# 06_FPGA_POWER.net
KiCad netlist of a schematic drawn in Altium Designer
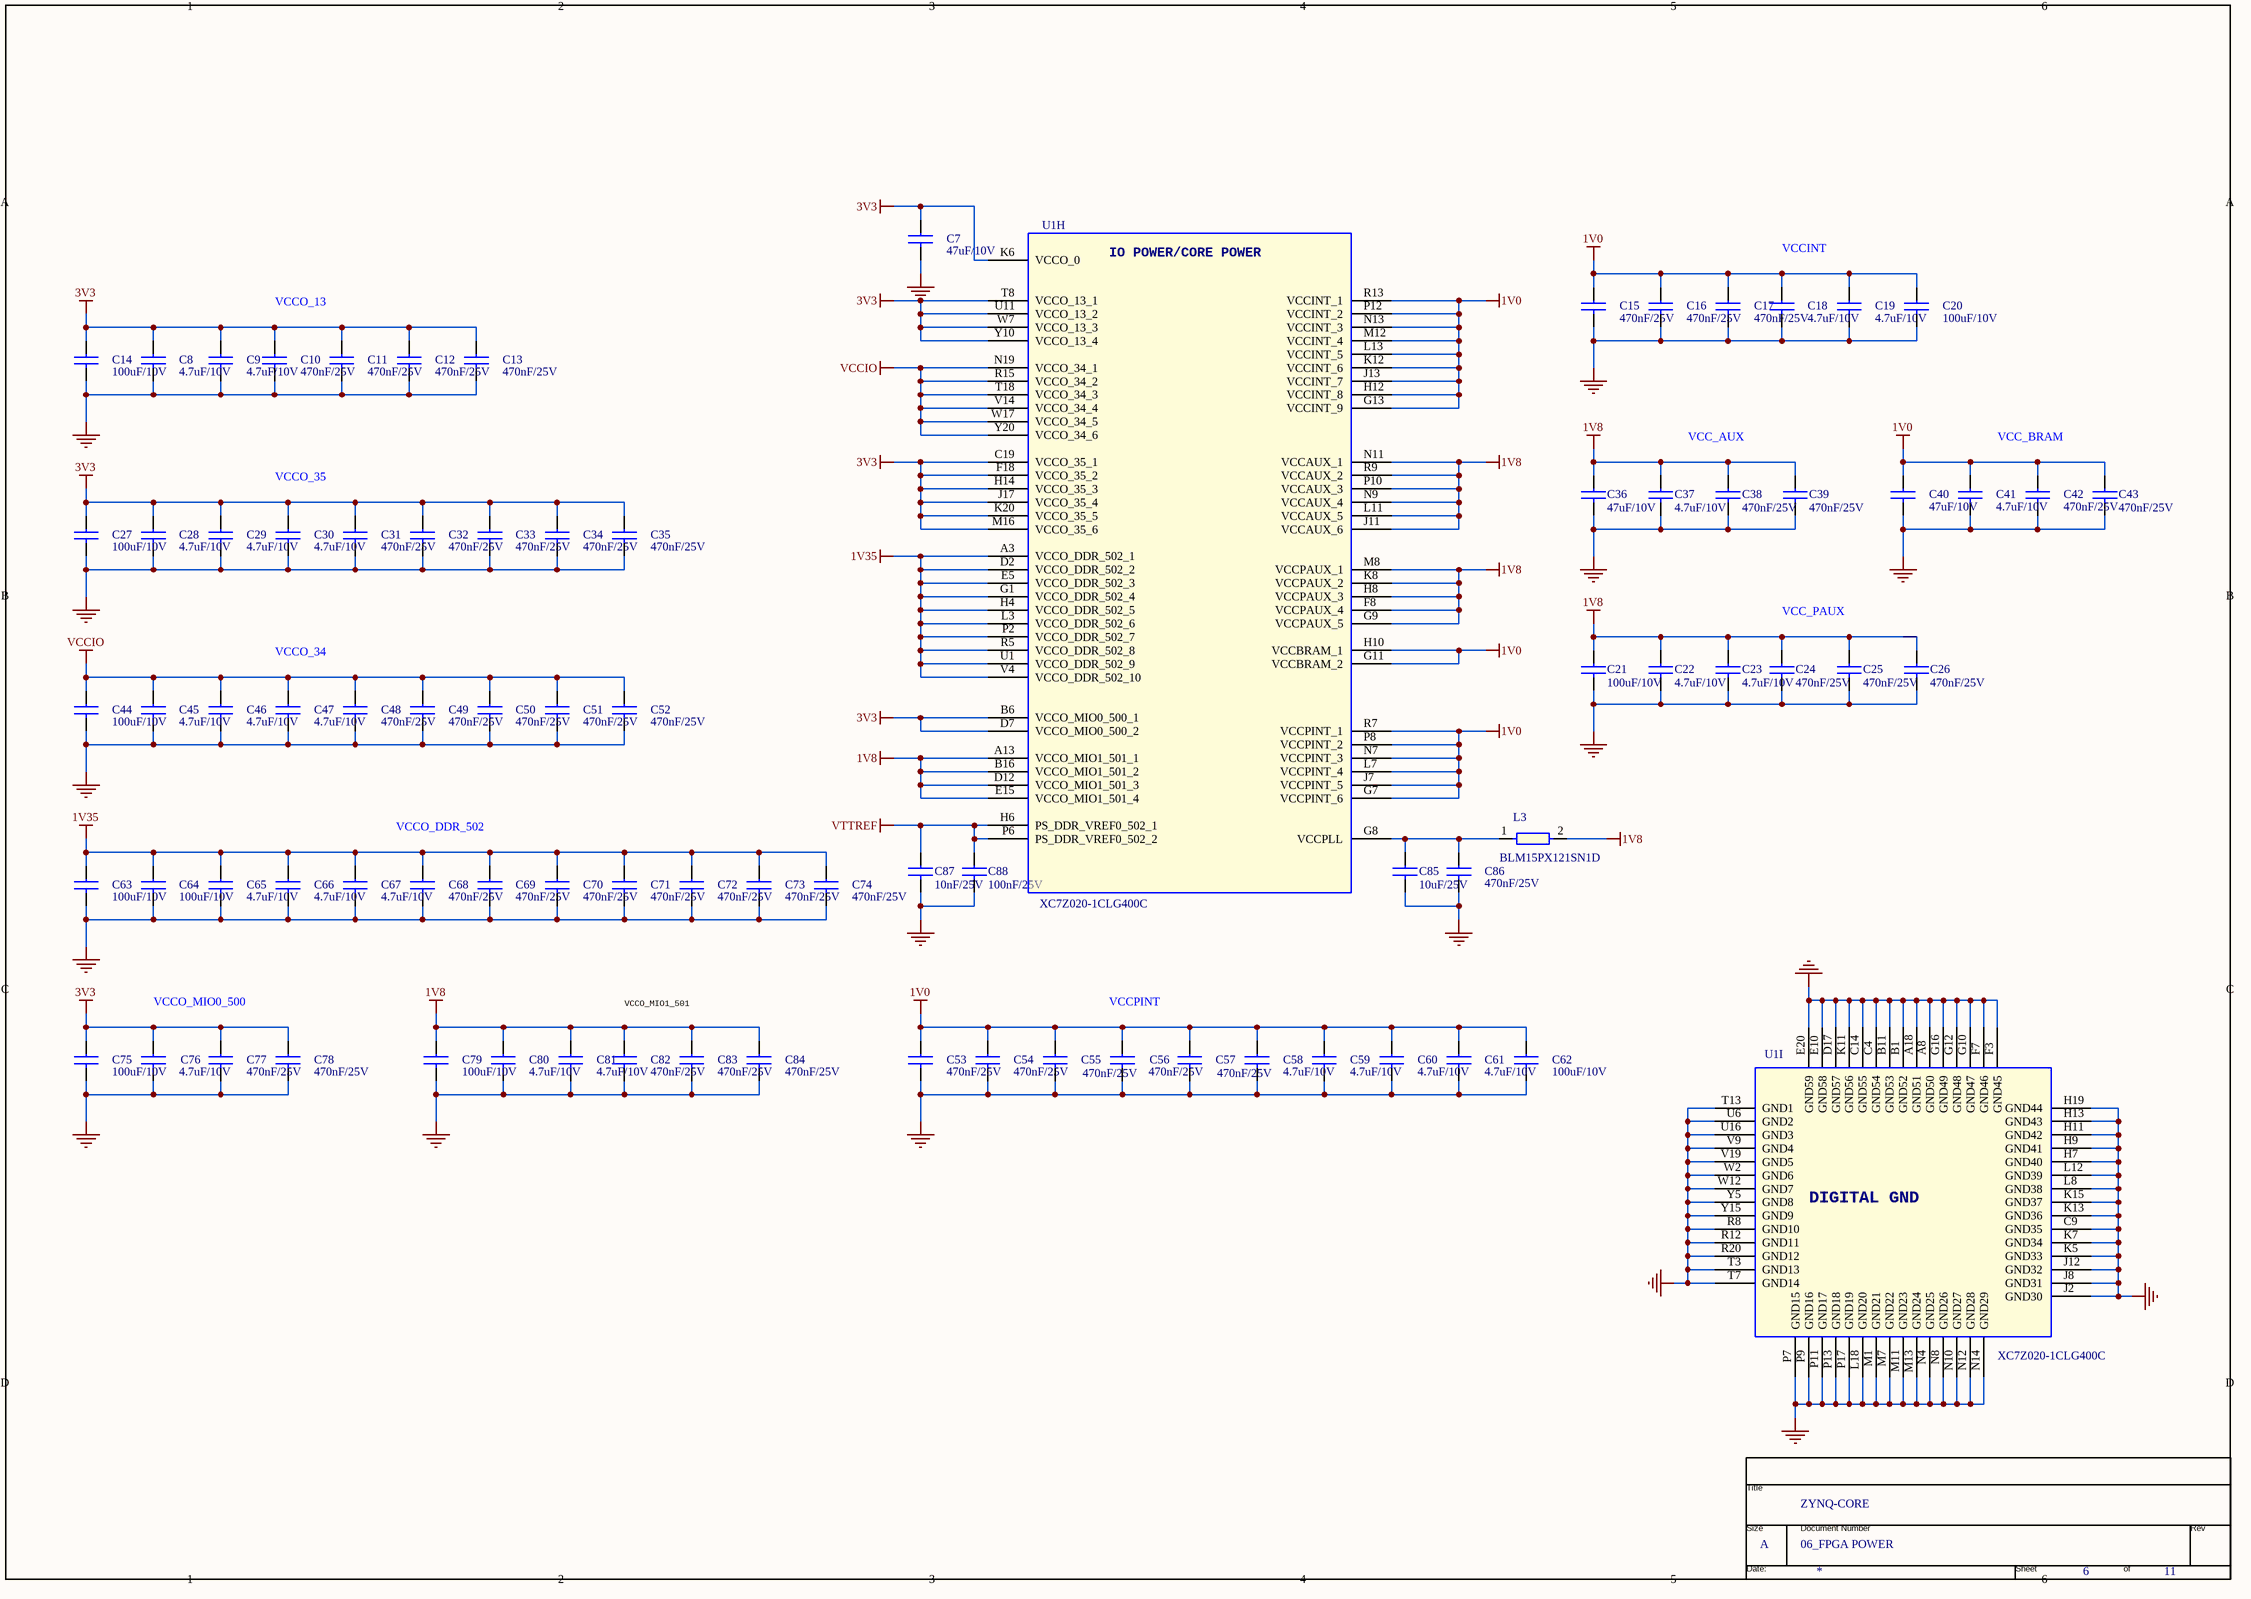
[diagram p0: 06_FPGA POWER.SchDoc]

(export (version "E")
  (design (tool "Eeschema 10.0.6"))
  (components
    (comp (ref "C7") (value "47uF/10V") (footprint "C0805") (libsource (lib "*") (part "CAP NP_Dup1")))
    (comp (ref "C8") (value "4.7uF/10V") (footprint "C0402") (libsource (lib "*") (part "CAP NP_Dup1")))
    (comp (ref "C9") (value "4.7uF/10V") (footprint "C0402") (libsource (lib "*") (part "CAP NP_Dup1")))
    (comp (ref "C10") (value "470nF/25V") (footprint "C0402") (libsource (lib "*") (part "CAP NP_Dup1")))
    (comp (ref "C11") (value "470nF/25V") (footprint "C0402") (libsource (lib "*") (part "CAP NP_Dup1")))
    (comp (ref "C12") (value "470nF/25V") (footprint "C0402") (libsource (lib "*") (part "CAP NP_Dup1")))
    (comp (ref "C13") (value "470nF/25V") (footprint "C0402") (libsource (lib "*") (part "CAP NP_Dup1")))
    (comp (ref "C14") (value "100uF/10V") (footprint "1206C-N") (libsource (lib "*") (part "CAP NP_Dup1")))
    (comp (ref "C15") (value "470nF/25V") (footprint "C0402") (libsource (lib "*") (part "CAP NP_Dup1")))
    (comp (ref "C16") (value "470nF/25V") (footprint "C0402") (libsource (lib "*") (part "CAP NP_Dup1")))
    (comp (ref "C17") (value "470nF/25V") (footprint "C0402") (libsource (lib "*") (part "CAP NP_Dup1")))
    (comp (ref "C18") (value "4.7uF/10V") (footprint "C0402") (libsource (lib "*") (part "CAP NP_Dup1")))
    (comp (ref "C19") (value "4.7uF/10V") (footprint "C0402") (libsource (lib "*") (part "CAP NP_Dup1")))
    (comp (ref "C20") (value "100uF/10V") (footprint "1206C-N") (libsource (lib "*") (part "CAP NP_Dup1")))
    (comp (ref "C21") (value "100uF/10V") (footprint "1206C-N") (libsource (lib "*") (part "CAP NP_Dup1")))
    (comp (ref "C22") (value "4.7uF/10V") (footprint "C0402") (libsource (lib "*") (part "CAP NP_Dup1")))
    (comp (ref "C23") (value "4.7uF/10V") (footprint "C0402") (libsource (lib "*") (part "CAP NP_Dup1")))
    (comp (ref "C24") (value "470nF/25V") (footprint "C0402") (libsource (lib "*") (part "CAP NP_Dup1")))
    (comp (ref "C25") (value "470nF/25V") (footprint "C0402") (libsource (lib "*") (part "CAP NP_Dup1")))
    (comp (ref "C26") (value "470nF/25V") (footprint "C0402") (libsource (lib "*") (part "CAP NP_Dup1")))
    (comp (ref "C27") (value "100uF/10V") (footprint "1206C-N") (libsource (lib "*") (part "CAP NP_Dup1")))
    (comp (ref "C28") (value "4.7uF/10V") (footprint "C0402") (libsource (lib "*") (part "CAP NP_Dup1")))
    (comp (ref "C29") (value "4.7uF/10V") (footprint "C0402") (libsource (lib "*") (part "CAP NP_Dup1")))
    (comp (ref "C30") (value "4.7uF/10V") (footprint "C0402") (libsource (lib "*") (part "CAP NP_Dup1")))
    (comp (ref "C31") (value "470nF/25V") (footprint "C0402") (libsource (lib "*") (part "CAP NP_Dup1")))
    (comp (ref "C32") (value "470nF/25V") (footprint "C0402") (libsource (lib "*") (part "CAP NP_Dup1")))
    (comp (ref "C33") (value "470nF/25V") (footprint "C0402") (libsource (lib "*") (part "CAP NP_Dup1")))
    (comp (ref "C34") (value "470nF/25V") (footprint "C0402") (libsource (lib "*") (part "CAP NP_Dup1")))
    (comp (ref "C35") (value "470nF/25V") (footprint "C0402") (libsource (lib "*") (part "CAP NP_Dup1")))
    (comp (ref "C36") (value "47uF/10V") (footprint "C0805") (libsource (lib "*") (part "CAP NP_Dup1")))
    (comp (ref "C37") (value "4.7uF/10V") (footprint "C0402") (libsource (lib "*") (part "CAP NP_Dup1")))
    (comp (ref "C38") (value "470nF/25V") (footprint "C0402") (libsource (lib "*") (part "CAP NP_Dup1")))
    (comp (ref "C39") (value "470nF/25V") (footprint "C0402") (libsource (lib "*") (part "CAP NP_Dup1")))
    (comp (ref "C40") (value "47uF/10V") (footprint "C0805") (libsource (lib "*") (part "CAP NP_Dup1")))
    (comp (ref "C41") (value "4.7uF/10V") (footprint "C0402") (libsource (lib "*") (part "CAP NP_Dup1")))
    (comp (ref "C42") (value "470nF/25V") (footprint "C0402") (libsource (lib "*") (part "CAP NP_Dup1")))
    (comp (ref "C43") (value "470nF/25V") (footprint "C0402") (libsource (lib "*") (part "CAP NP_Dup1")))
    (comp (ref "C44") (value "100uF/10V") (footprint "1206C-N") (libsource (lib "*") (part "CAP NP_Dup1")))
    (comp (ref "C45") (value "4.7uF/10V") (footprint "C0402") (libsource (lib "*") (part "CAP NP_Dup1")))
    (comp (ref "C46") (value "4.7uF/10V") (footprint "C0402") (libsource (lib "*") (part "CAP NP_Dup1")))
    (comp (ref "C47") (value "4.7uF/10V") (footprint "C0402") (libsource (lib "*") (part "CAP NP_Dup1")))
    (comp (ref "C48") (value "470nF/25V") (footprint "C0402") (libsource (lib "*") (part "CAP NP_Dup1")))
    (comp (ref "C49") (value "470nF/25V") (footprint "C0402") (libsource (lib "*") (part "CAP NP_Dup1")))
    (comp (ref "C50") (value "470nF/25V") (footprint "C0402") (libsource (lib "*") (part "CAP NP_Dup1")))
    (comp (ref "C51") (value "470nF/25V") (footprint "C0402") (libsource (lib "*") (part "CAP NP_Dup1")))
    (comp (ref "C52") (value "470nF/25V") (footprint "C0402") (libsource (lib "*") (part "CAP NP_Dup1")))
    (comp (ref "C53") (value "470nF/25V") (footprint "C0402") (libsource (lib "*") (part "CAP NP_Dup1")))
    (comp (ref "C54") (value "470nF/25V") (footprint "C0402") (libsource (lib "*") (part "CAP NP_Dup1")))
    (comp (ref "C55") (value "470nF/25V") (footprint "C0402") (libsource (lib "*") (part "CAP NP_Dup1")))
    (comp (ref "C56") (value "470nF/25V") (footprint "C0402") (libsource (lib "*") (part "CAP NP_Dup1")))
    (comp (ref "C57") (value "470nF/25V") (footprint "C0402") (libsource (lib "*") (part "CAP NP_Dup1")))
    (comp (ref "C58") (value "4.7uF/10V") (footprint "C0402") (libsource (lib "*") (part "CAP NP_Dup1")))
    (comp (ref "C59") (value "4.7uF/10V") (footprint "C0402") (libsource (lib "*") (part "CAP NP_Dup1")))
    (comp (ref "C60") (value "4.7uF/10V") (footprint "C0402") (libsource (lib "*") (part "CAP NP_Dup1")))
    (comp (ref "C61") (value "4.7uF/10V") (footprint "C0402") (libsource (lib "*") (part "CAP NP_Dup1")))
    (comp (ref "C62") (value "100uF/10V") (footprint "1206C-N") (libsource (lib "*") (part "CAP NP_Dup1")))
    (comp (ref "C63") (value "100uF/10V") (footprint "1206C-N") (libsource (lib "*") (part "CAP NP_Dup1")))
    (comp (ref "C64") (value "100uF/10V") (footprint "1206C-N") (libsource (lib "*") (part "CAP NP_Dup1")))
    (comp (ref "C65") (value "4.7uF/10V") (footprint "C0402") (libsource (lib "*") (part "CAP NP_Dup1")))
    (comp (ref "C66") (value "4.7uF/10V") (footprint "C0402") (libsource (lib "*") (part "CAP NP_Dup1")))
    (comp (ref "C67") (value "4.7uF/10V") (footprint "C0402") (libsource (lib "*") (part "CAP NP_Dup1")))
    (comp (ref "C68") (value "470nF/25V") (footprint "C0402") (libsource (lib "*") (part "CAP NP_Dup1")))
    (comp (ref "C69") (value "470nF/25V") (footprint "C0402") (libsource (lib "*") (part "CAP NP_Dup1")))
    (comp (ref "C70") (value "470nF/25V") (footprint "C0402") (libsource (lib "*") (part "CAP NP_Dup1")))
    (comp (ref "C71") (value "470nF/25V") (footprint "C0402") (libsource (lib "*") (part "CAP NP_Dup1")))
    (comp (ref "C72") (value "470nF/25V") (footprint "C0402") (libsource (lib "*") (part "CAP NP_Dup1")))
    (comp (ref "C73") (value "470nF/25V") (footprint "C0402") (libsource (lib "*") (part "CAP NP_Dup1")))
    (comp (ref "C74") (value "470nF/25V") (footprint "C0402") (libsource (lib "*") (part "CAP NP_Dup1")))
    (comp (ref "C75") (value "100uF/10V") (footprint "1206C-N") (libsource (lib "*") (part "CAP NP_Dup1")))
    (comp (ref "C76") (value "4.7uF/10V") (footprint "C0402") (libsource (lib "*") (part "CAP NP_Dup1")))
    (comp (ref "C77") (value "470nF/25V") (footprint "C0402") (libsource (lib "*") (part "CAP NP_Dup1")))
    (comp (ref "C78") (value "470nF/25V") (footprint "C0402") (libsource (lib "*") (part "CAP NP_Dup1")))
    (comp (ref "C79") (value "100uF/10V") (footprint "1206C-N") (libsource (lib "*") (part "CAP NP_Dup1")))
    (comp (ref "C80") (value "4.7uF/10V") (footprint "C0402") (libsource (lib "*") (part "CAP NP_Dup1")))
    (comp (ref "C81") (value "4.7uF/10V") (footprint "C0402") (libsource (lib "*") (part "CAP NP_Dup1")))
    (comp (ref "C82") (value "470nF/25V") (footprint "C0402") (libsource (lib "*") (part "CAP NP_Dup1")))
    (comp (ref "C83") (value "470nF/25V") (footprint "C0402") (libsource (lib "*") (part "CAP NP_Dup1")))
    (comp (ref "C84") (value "470nF/25V") (footprint "C0402") (libsource (lib "*") (part "CAP NP_Dup1")))
    (comp (ref "C85") (value "10uF/25V") (footprint "C0603") (libsource (lib "*") (part "CAP NP_Dup1")))
    (comp (ref "C86") (value "470nF/25V") (footprint "C0402") (libsource (lib "*") (part "CAP NP_Dup1")))
    (comp (ref "C87") (value "10nF/25V") (footprint "C0402") (libsource (lib "*") (part "CAP NP_Dup1")))
    (comp (ref "C88") (value "100nF/25V") (footprint "C0402") (libsource (lib "*") (part "CAP NP_Dup1")))
    (comp (ref "L3") (value "BLM15PX121SN1D") (footprint "L0402") (libsource (lib "*") (part "FB")))
    (comp (ref "U1")
      (value "XC7Z020-1CLG400C")
      (footprint "CLG400")
      (libsource (lib "*") (part "Zynq7010/7020"))
    )
  )
  (nets
    (net (code "1") (name "1V0") (class "Default")
      (node (ref "C15") (pin "1") (pinfunction "1_1") (pintype "passive"))
      (node (ref "C16") (pin "1") (pinfunction "1_1") (pintype "passive"))
      (node (ref "C17") (pin "1") (pinfunction "1_1") (pintype "passive"))
      (node (ref "C18") (pin "1") (pinfunction "1_1") (pintype "passive"))
      (node (ref "C19") (pin "1") (pinfunction "1_1") (pintype "passive"))
      (node (ref "C20") (pin "1") (pinfunction "1_1") (pintype "passive"))
      (node (ref "C40") (pin "1") (pinfunction "1_1") (pintype "passive"))
      (node (ref "C41") (pin "1") (pinfunction "1_1") (pintype "passive"))
      (node (ref "C42") (pin "1") (pinfunction "1_1") (pintype "passive"))
      (node (ref "C43") (pin "1") (pinfunction "1_1") (pintype "passive"))
      (node (ref "C53") (pin "1") (pinfunction "1_1") (pintype "passive"))
      (node (ref "C54") (pin "1") (pinfunction "1_1") (pintype "passive"))
      (node (ref "C55") (pin "1") (pinfunction "1_1") (pintype "passive"))
      (node (ref "C56") (pin "1") (pinfunction "1_1") (pintype "passive"))
      (node (ref "C57") (pin "1") (pinfunction "1_1") (pintype "passive"))
      (node (ref "C58") (pin "1") (pinfunction "1_1") (pintype "passive"))
      (node (ref "C59") (pin "1") (pinfunction "1_1") (pintype "passive"))
      (node (ref "C60") (pin "1") (pinfunction "1_1") (pintype "passive"))
      (node (ref "C61") (pin "1") (pinfunction "1_1") (pintype "passive"))
      (node (ref "C62") (pin "1") (pinfunction "1_1") (pintype "passive"))
      (node (ref "U1") (pin "G11") (pinfunction "VCCBRAM_2_G11") (pintype "passive"))
      (node (ref "U1") (pin "G13") (pinfunction "VCCINT_9_G13") (pintype "passive"))
      (node (ref "U1") (pin "G7") (pinfunction "VCCPINT_6_G7") (pintype "passive"))
      (node (ref "U1") (pin "H10") (pinfunction "VCCBRAM_1_H10") (pintype "passive"))
      (node (ref "U1") (pin "H12") (pinfunction "VCCINT_8_H12") (pintype "passive"))
      (node (ref "U1") (pin "J13") (pinfunction "VCCINT_7_J13") (pintype "passive"))
      (node (ref "U1") (pin "J7") (pinfunction "VCCPINT_5_J7") (pintype "passive"))
      (node (ref "U1") (pin "K12") (pinfunction "VCCINT_6_K12") (pintype "passive"))
      (node (ref "U1") (pin "L13") (pinfunction "VCCINT_5_L13") (pintype "passive"))
      (node (ref "U1") (pin "L7") (pinfunction "VCCPINT_4_L7") (pintype "passive"))
      (node (ref "U1") (pin "M12") (pinfunction "VCCINT_4_M12") (pintype "passive"))
      (node (ref "U1") (pin "N13") (pinfunction "VCCINT_3_N13") (pintype "passive"))
      (node (ref "U1") (pin "N7") (pinfunction "VCCPINT_3_N7") (pintype "passive"))
      (node (ref "U1") (pin "P12") (pinfunction "VCCINT_2_P12") (pintype "passive"))
      (node (ref "U1") (pin "P8") (pinfunction "VCCPINT_2_P8") (pintype "passive"))
      (node (ref "U1") (pin "R13") (pinfunction "VCCINT_1_R13") (pintype "passive"))
      (node (ref "U1") (pin "R7") (pinfunction "VCCPINT_1_R7") (pintype "passive"))
    )
    (net (code "2") (name "1V8") (class "Default")
      (node (ref "C21") (pin "1") (pinfunction "1_1") (pintype "passive"))
      (node (ref "C22") (pin "1") (pinfunction "1_1") (pintype "passive"))
      (node (ref "C23") (pin "1") (pinfunction "1_1") (pintype "passive"))
      (node (ref "C24") (pin "1") (pinfunction "1_1") (pintype "passive"))
      (node (ref "C25") (pin "1") (pinfunction "1_1") (pintype "passive"))
      (node (ref "C26") (pin "1") (pinfunction "1_1") (pintype "passive"))
      (node (ref "C36") (pin "1") (pinfunction "1_1") (pintype "passive"))
      (node (ref "C37") (pin "1") (pinfunction "1_1") (pintype "passive"))
      (node (ref "C38") (pin "1") (pinfunction "1_1") (pintype "passive"))
      (node (ref "C39") (pin "1") (pinfunction "1_1") (pintype "passive"))
      (node (ref "C79") (pin "1") (pinfunction "1_1") (pintype "passive"))
      (node (ref "C80") (pin "1") (pinfunction "1_1") (pintype "passive"))
      (node (ref "C81") (pin "1") (pinfunction "1_1") (pintype "passive"))
      (node (ref "C82") (pin "1") (pinfunction "1_1") (pintype "passive"))
      (node (ref "C83") (pin "1") (pinfunction "1_1") (pintype "passive"))
      (node (ref "C84") (pin "1") (pinfunction "1_1") (pintype "passive"))
      (node (ref "L3") (pin "2") (pinfunction "2_2") (pintype "passive"))
      (node (ref "U1") (pin "A13") (pinfunction "VCCO_MIO1_501_1_A13") (pintype "passive"))
      (node (ref "U1") (pin "B16") (pinfunction "VCCO_MIO1_501_2_B16") (pintype "passive"))
      (node (ref "U1") (pin "D12") (pinfunction "VCCO_MIO1_501_3_D12") (pintype "passive"))
      (node (ref "U1") (pin "E15") (pinfunction "VCCO_MIO1_501_4_E15") (pintype "passive"))
      (node (ref "U1") (pin "F8") (pinfunction "VCCPAUX_4_F8") (pintype "passive"))
      (node (ref "U1") (pin "G9") (pinfunction "VCCPAUX_5_G9") (pintype "passive"))
      (node (ref "U1") (pin "H8") (pinfunction "VCCPAUX_3_H8") (pintype "passive"))
      (node (ref "U1") (pin "J11") (pinfunction "VCCAUX_6_J11") (pintype "passive"))
      (node (ref "U1") (pin "K8") (pinfunction "VCCPAUX_2_K8") (pintype "passive"))
      (node (ref "U1") (pin "L11") (pinfunction "VCCAUX_5_L11") (pintype "passive"))
      (node (ref "U1") (pin "M8") (pinfunction "VCCPAUX_1_M8") (pintype "passive"))
      (node (ref "U1") (pin "N11") (pinfunction "VCCAUX_1_N11") (pintype "passive"))
      (node (ref "U1") (pin "N9") (pinfunction "VCCAUX_4_N9") (pintype "passive"))
      (node (ref "U1") (pin "P10") (pinfunction "VCCAUX_3_P10") (pintype "passive"))
      (node (ref "U1") (pin "R9") (pinfunction "VCCAUX_2_R9") (pintype "passive"))
    )
    (net (code "3") (name "1V35") (class "Default")
      (node (ref "C63") (pin "1") (pinfunction "1_1") (pintype "passive"))
      (node (ref "C64") (pin "1") (pinfunction "1_1") (pintype "passive"))
      (node (ref "C65") (pin "1") (pinfunction "1_1") (pintype "passive"))
      (node (ref "C66") (pin "1") (pinfunction "1_1") (pintype "passive"))
      (node (ref "C67") (pin "1") (pinfunction "1_1") (pintype "passive"))
      (node (ref "C68") (pin "1") (pinfunction "1_1") (pintype "passive"))
      (node (ref "C69") (pin "1") (pinfunction "1_1") (pintype "passive"))
      (node (ref "C70") (pin "1") (pinfunction "1_1") (pintype "passive"))
      (node (ref "C71") (pin "1") (pinfunction "1_1") (pintype "passive"))
      (node (ref "C72") (pin "1") (pinfunction "1_1") (pintype "passive"))
      (node (ref "C73") (pin "1") (pinfunction "1_1") (pintype "passive"))
      (node (ref "C74") (pin "1") (pinfunction "1_1") (pintype "passive"))
      (node (ref "U1") (pin "A3") (pinfunction "VCCO_DDR_502_1_A3") (pintype "passive"))
      (node (ref "U1") (pin "D2") (pinfunction "VCCO_DDR_502_2_D2") (pintype "passive"))
      (node (ref "U1") (pin "E5") (pinfunction "VCCO_DDR_502_3_E5") (pintype "passive"))
      (node (ref "U1") (pin "G1") (pinfunction "VCCO_DDR_502_4_G1") (pintype "passive"))
      (node (ref "U1") (pin "H4") (pinfunction "VCCO_DDR_502_5_H4") (pintype "passive"))
      (node (ref "U1") (pin "L3") (pinfunction "VCCO_DDR_502_6_L3") (pintype "passive"))
      (node (ref "U1") (pin "P2") (pinfunction "VCCO_DDR_502_7_P2") (pintype "passive"))
      (node (ref "U1") (pin "R5") (pinfunction "VCCO_DDR_502_8_R5") (pintype "passive"))
      (node (ref "U1") (pin "U1") (pinfunction "VCCO_DDR_502_9_U1") (pintype "passive"))
      (node (ref "U1") (pin "V4") (pinfunction "VCCO_DDR_502_10_V4") (pintype "passive"))
    )
    (net (code "4") (name "3V3") (class "Default")
      (node (ref "C10") (pin "1") (pinfunction "1_1") (pintype "passive"))
      (node (ref "C11") (pin "1") (pinfunction "1_1") (pintype "passive"))
      (node (ref "C12") (pin "1") (pinfunction "1_1") (pintype "passive"))
      (node (ref "C13") (pin "1") (pinfunction "1_1") (pintype "passive"))
      (node (ref "C14") (pin "1") (pinfunction "1_1") (pintype "passive"))
      (node (ref "C27") (pin "1") (pinfunction "1_1") (pintype "passive"))
      (node (ref "C28") (pin "1") (pinfunction "1_1") (pintype "passive"))
      (node (ref "C29") (pin "1") (pinfunction "1_1") (pintype "passive"))
      (node (ref "C30") (pin "1") (pinfunction "1_1") (pintype "passive"))
      (node (ref "C31") (pin "1") (pinfunction "1_1") (pintype "passive"))
      (node (ref "C32") (pin "1") (pinfunction "1_1") (pintype "passive"))
      (node (ref "C33") (pin "1") (pinfunction "1_1") (pintype "passive"))
      (node (ref "C34") (pin "1") (pinfunction "1_1") (pintype "passive"))
      (node (ref "C35") (pin "1") (pinfunction "1_1") (pintype "passive"))
      (node (ref "C7") (pin "1") (pinfunction "1_1") (pintype "passive"))
      (node (ref "C75") (pin "1") (pinfunction "1_1") (pintype "passive"))
      (node (ref "C76") (pin "1") (pinfunction "1_1") (pintype "passive"))
      (node (ref "C77") (pin "1") (pinfunction "1_1") (pintype "passive"))
      (node (ref "C78") (pin "1") (pinfunction "1_1") (pintype "passive"))
      (node (ref "C8") (pin "1") (pinfunction "1_1") (pintype "passive"))
      (node (ref "C9") (pin "1") (pinfunction "1_1") (pintype "passive"))
      (node (ref "U1") (pin "B6") (pinfunction "VCCO_MIO0_500_1_B6") (pintype "passive"))
      (node (ref "U1") (pin "C19") (pinfunction "VCCO_35_1_C19") (pintype "passive"))
      (node (ref "U1") (pin "D7") (pinfunction "VCCO_MIO0_500_2_D7") (pintype "passive"))
      (node (ref "U1") (pin "F18") (pinfunction "VCCO_35_2_F18") (pintype "passive"))
      (node (ref "U1") (pin "H14") (pinfunction "VCCO_35_3_H14") (pintype "passive"))
      (node (ref "U1") (pin "J17") (pinfunction "VCCO_35_4_J17") (pintype "passive"))
      (node (ref "U1") (pin "K20") (pinfunction "VCCO_35_5_K20") (pintype "passive"))
      (node (ref "U1") (pin "K6") (pinfunction "VCCO_0_K6") (pintype "passive"))
      (node (ref "U1") (pin "M16") (pinfunction "VCCO_35_6_M16") (pintype "passive"))
      (node (ref "U1") (pin "T8") (pinfunction "VCCO_13_1_T8") (pintype "passive"))
      (node (ref "U1") (pin "U11") (pinfunction "VCCO_13_2_U11") (pintype "passive"))
      (node (ref "U1") (pin "W7") (pinfunction "VCCO_13_3_W7") (pintype "passive"))
      (node (ref "U1") (pin "Y10") (pinfunction "VCCO_13_4_Y10") (pintype "passive"))
    )
    (net (code "5") (name "GND") (class "Default")
      (node (ref "C10") (pin "2") (pinfunction "2_2") (pintype "passive"))
      (node (ref "C11") (pin "2") (pinfunction "2_2") (pintype "passive"))
      (node (ref "C12") (pin "2") (pinfunction "2_2") (pintype "passive"))
      (node (ref "C13") (pin "2") (pinfunction "2_2") (pintype "passive"))
      (node (ref "C14") (pin "2") (pinfunction "2_2") (pintype "passive"))
      (node (ref "C15") (pin "2") (pinfunction "2_2") (pintype "passive"))
      (node (ref "C16") (pin "2") (pinfunction "2_2") (pintype "passive"))
      (node (ref "C17") (pin "2") (pinfunction "2_2") (pintype "passive"))
      (node (ref "C18") (pin "2") (pinfunction "2_2") (pintype "passive"))
      (node (ref "C19") (pin "2") (pinfunction "2_2") (pintype "passive"))
      (node (ref "C20") (pin "2") (pinfunction "2_2") (pintype "passive"))
      (node (ref "C21") (pin "2") (pinfunction "2_2") (pintype "passive"))
      (node (ref "C22") (pin "2") (pinfunction "2_2") (pintype "passive"))
      (node (ref "C23") (pin "2") (pinfunction "2_2") (pintype "passive"))
      (node (ref "C24") (pin "2") (pinfunction "2_2") (pintype "passive"))
      (node (ref "C25") (pin "2") (pinfunction "2_2") (pintype "passive"))
      (node (ref "C26") (pin "2") (pinfunction "2_2") (pintype "passive"))
      (node (ref "C27") (pin "2") (pinfunction "2_2") (pintype "passive"))
      (node (ref "C28") (pin "2") (pinfunction "2_2") (pintype "passive"))
      (node (ref "C29") (pin "2") (pinfunction "2_2") (pintype "passive"))
      (node (ref "C30") (pin "2") (pinfunction "2_2") (pintype "passive"))
      (node (ref "C31") (pin "2") (pinfunction "2_2") (pintype "passive"))
      (node (ref "C32") (pin "2") (pinfunction "2_2") (pintype "passive"))
      (node (ref "C33") (pin "2") (pinfunction "2_2") (pintype "passive"))
      (node (ref "C34") (pin "2") (pinfunction "2_2") (pintype "passive"))
      (node (ref "C35") (pin "2") (pinfunction "2_2") (pintype "passive"))
      (node (ref "C36") (pin "2") (pinfunction "2_2") (pintype "passive"))
      (node (ref "C37") (pin "2") (pinfunction "2_2") (pintype "passive"))
      (node (ref "C38") (pin "2") (pinfunction "2_2") (pintype "passive"))
      (node (ref "C39") (pin "2") (pinfunction "2_2") (pintype "passive"))
      (node (ref "C40") (pin "2") (pinfunction "2_2") (pintype "passive"))
      (node (ref "C41") (pin "2") (pinfunction "2_2") (pintype "passive"))
      (node (ref "C42") (pin "2") (pinfunction "2_2") (pintype "passive"))
      (node (ref "C43") (pin "2") (pinfunction "2_2") (pintype "passive"))
      (node (ref "C44") (pin "2") (pinfunction "2_2") (pintype "passive"))
      (node (ref "C45") (pin "2") (pinfunction "2_2") (pintype "passive"))
      (node (ref "C46") (pin "2") (pinfunction "2_2") (pintype "passive"))
      (node (ref "C47") (pin "2") (pinfunction "2_2") (pintype "passive"))
      (node (ref "C48") (pin "2") (pinfunction "2_2") (pintype "passive"))
      (node (ref "C49") (pin "2") (pinfunction "2_2") (pintype "passive"))
      (node (ref "C50") (pin "2") (pinfunction "2_2") (pintype "passive"))
      (node (ref "C51") (pin "2") (pinfunction "2_2") (pintype "passive"))
      (node (ref "C52") (pin "2") (pinfunction "2_2") (pintype "passive"))
      (node (ref "C53") (pin "2") (pinfunction "2_2") (pintype "passive"))
      (node (ref "C54") (pin "2") (pinfunction "2_2") (pintype "passive"))
      (node (ref "C55") (pin "2") (pinfunction "2_2") (pintype "passive"))
      (node (ref "C56") (pin "2") (pinfunction "2_2") (pintype "passive"))
      (node (ref "C57") (pin "2") (pinfunction "2_2") (pintype "passive"))
      (node (ref "C58") (pin "2") (pinfunction "2_2") (pintype "passive"))
      (node (ref "C59") (pin "2") (pinfunction "2_2") (pintype "passive"))
      (node (ref "C60") (pin "2") (pinfunction "2_2") (pintype "passive"))
      (node (ref "C61") (pin "2") (pinfunction "2_2") (pintype "passive"))
      (node (ref "C62") (pin "2") (pinfunction "2_2") (pintype "passive"))
      (node (ref "C63") (pin "2") (pinfunction "2_2") (pintype "passive"))
      (node (ref "C64") (pin "2") (pinfunction "2_2") (pintype "passive"))
      (node (ref "C65") (pin "2") (pinfunction "2_2") (pintype "passive"))
      (node (ref "C66") (pin "2") (pinfunction "2_2") (pintype "passive"))
      (node (ref "C67") (pin "2") (pinfunction "2_2") (pintype "passive"))
      (node (ref "C68") (pin "2") (pinfunction "2_2") (pintype "passive"))
      (node (ref "C69") (pin "2") (pinfunction "2_2") (pintype "passive"))
      (node (ref "C7") (pin "2") (pinfunction "2_2") (pintype "passive"))
      (node (ref "C70") (pin "2") (pinfunction "2_2") (pintype "passive"))
      (node (ref "C71") (pin "2") (pinfunction "2_2") (pintype "passive"))
      (node (ref "C72") (pin "2") (pinfunction "2_2") (pintype "passive"))
      (node (ref "C73") (pin "2") (pinfunction "2_2") (pintype "passive"))
      (node (ref "C74") (pin "2") (pinfunction "2_2") (pintype "passive"))
      (node (ref "C75") (pin "2") (pinfunction "2_2") (pintype "passive"))
      (node (ref "C76") (pin "2") (pinfunction "2_2") (pintype "passive"))
      (node (ref "C77") (pin "2") (pinfunction "2_2") (pintype "passive"))
      (node (ref "C78") (pin "2") (pinfunction "2_2") (pintype "passive"))
      (node (ref "C79") (pin "2") (pinfunction "2_2") (pintype "passive"))
      (node (ref "C8") (pin "2") (pinfunction "2_2") (pintype "passive"))
      (node (ref "C80") (pin "2") (pinfunction "2_2") (pintype "passive"))
      (node (ref "C81") (pin "2") (pinfunction "2_2") (pintype "passive"))
      (node (ref "C82") (pin "2") (pinfunction "2_2") (pintype "passive"))
      (node (ref "C83") (pin "2") (pinfunction "2_2") (pintype "passive"))
      (node (ref "C84") (pin "2") (pinfunction "2_2") (pintype "passive"))
      (node (ref "C85") (pin "2") (pinfunction "2_2") (pintype "passive"))
      (node (ref "C86") (pin "2") (pinfunction "2_2") (pintype "passive"))
      (node (ref "C87") (pin "2") (pinfunction "2_2") (pintype "passive"))
      (node (ref "C88") (pin "2") (pinfunction "2_2") (pintype "passive"))
      (node (ref "C9") (pin "2") (pinfunction "2_2") (pintype "passive"))
      (node (ref "U1") (pin "A18") (pinfunction "GND51_A18") (pintype "passive"))
      (node (ref "U1") (pin "A8") (pinfunction "GND50_A8") (pintype "passive"))
      (node (ref "U1") (pin "B1") (pinfunction "GND52_B1") (pintype "passive"))
      (node (ref "U1") (pin "B11") (pinfunction "GND53_B11") (pintype "passive"))
      (node (ref "U1") (pin "C14") (pinfunction "GND55_C14") (pintype "passive"))
      (node (ref "U1") (pin "C4") (pinfunction "GND54_C4") (pintype "passive"))
      (node (ref "U1") (pin "C9") (pinfunction "GND35_C9") (pintype "passive"))
      (node (ref "U1") (pin "D17") (pinfunction "GND57_D17") (pintype "passive"))
      (node (ref "U1") (pin "E10") (pinfunction "GND58_E10") (pintype "passive"))
      (node (ref "U1") (pin "E20") (pinfunction "GND59_E20") (pintype "passive"))
      (node (ref "U1") (pin "F3") (pinfunction "GND45_F3") (pintype "passive"))
      (node (ref "U1") (pin "F7") (pinfunction "GND46_F7") (pintype "passive"))
      (node (ref "U1") (pin "G10") (pinfunction "GND47_G10") (pintype "passive"))
      (node (ref "U1") (pin "G12") (pinfunction "GND48_G12") (pintype "passive"))
      (node (ref "U1") (pin "G16") (pinfunction "GND49_G16") (pintype "passive"))
      (node (ref "U1") (pin "H11") (pinfunction "GND42_H11") (pintype "passive"))
      (node (ref "U1") (pin "H13") (pinfunction "GND43_H13") (pintype "passive"))
      (node (ref "U1") (pin "H19") (pinfunction "GND44_H19") (pintype "passive"))
      (node (ref "U1") (pin "H7") (pinfunction "GND40_H7") (pintype "passive"))
      (node (ref "U1") (pin "H9") (pinfunction "GND41_H9") (pintype "passive"))
      (node (ref "U1") (pin "J12") (pinfunction "GND32_J12") (pintype "passive"))
      (node (ref "U1") (pin "J2") (pinfunction "GND30_J2") (pintype "passive"))
      (node (ref "U1") (pin "J8") (pinfunction "GND31_J8") (pintype "passive"))
      (node (ref "U1") (pin "K11") (pinfunction "GND56_K11") (pintype "passive"))
      (node (ref "U1") (pin "K13") (pinfunction "GND36_K13") (pintype "passive"))
      (node (ref "U1") (pin "K15") (pinfunction "GND37_K15") (pintype "passive"))
      (node (ref "U1") (pin "K5") (pinfunction "GND33_K5") (pintype "passive"))
      (node (ref "U1") (pin "K7") (pinfunction "GND34_K7") (pintype "passive"))
      (node (ref "U1") (pin "L12") (pinfunction "GND39_L12") (pintype "passive"))
      (node (ref "U1") (pin "L18") (pinfunction "GND20_L18") (pintype "passive"))
      (node (ref "U1") (pin "L8") (pinfunction "GND38_L8") (pintype "passive"))
      (node (ref "U1") (pin "M1") (pinfunction "GND21_M1") (pintype "passive"))
      (node (ref "U1") (pin "M11") (pinfunction "GND23_M11") (pintype "passive"))
      (node (ref "U1") (pin "M13") (pinfunction "GND24_M13") (pintype "passive"))
      (node (ref "U1") (pin "M7") (pinfunction "GND22_M7") (pintype "passive"))
      (node (ref "U1") (pin "N10") (pinfunction "GND27_N10") (pintype "passive"))
      (node (ref "U1") (pin "N12") (pinfunction "GND28_N12") (pintype "passive"))
      (node (ref "U1") (pin "N14") (pinfunction "GND29_N14") (pintype "passive"))
      (node (ref "U1") (pin "N4") (pinfunction "GND25_N4") (pintype "passive"))
      (node (ref "U1") (pin "N8") (pinfunction "GND26_N8") (pintype "passive"))
      (node (ref "U1") (pin "P11") (pinfunction "GND17_P11") (pintype "passive"))
      (node (ref "U1") (pin "P13") (pinfunction "GND18_P13") (pintype "passive"))
      (node (ref "U1") (pin "P17") (pinfunction "GND19_P17") (pintype "passive"))
      (node (ref "U1") (pin "P7") (pinfunction "GND15_P7") (pintype "passive"))
      (node (ref "U1") (pin "P9") (pinfunction "GND16_P9") (pintype "passive"))
      (node (ref "U1") (pin "R12") (pinfunction "GND11_R12") (pintype "passive"))
      (node (ref "U1") (pin "R20") (pinfunction "GND12_R20") (pintype "passive"))
      (node (ref "U1") (pin "R8") (pinfunction "GND10_R8") (pintype "passive"))
      (node (ref "U1") (pin "T13") (pinfunction "GND1_T13") (pintype "passive"))
      (node (ref "U1") (pin "T3") (pinfunction "GND13_T3") (pintype "passive"))
      (node (ref "U1") (pin "T7") (pinfunction "GND14_T7") (pintype "passive"))
      (node (ref "U1") (pin "U16") (pinfunction "GND3_U16") (pintype "passive"))
      (node (ref "U1") (pin "U6") (pinfunction "GND2_U6") (pintype "passive"))
      (node (ref "U1") (pin "V19") (pinfunction "GND5_V19") (pintype "passive"))
      (node (ref "U1") (pin "V9") (pinfunction "GND4_V9") (pintype "passive"))
      (node (ref "U1") (pin "W12") (pinfunction "GND7_W12") (pintype "passive"))
      (node (ref "U1") (pin "W2") (pinfunction "GND6_W2") (pintype "passive"))
      (node (ref "U1") (pin "Y15") (pinfunction "GND9_Y15") (pintype "passive"))
      (node (ref "U1") (pin "Y5") (pinfunction "GND8_Y5") (pintype "passive"))
    )
    (net (code "6") (name "Net-(U1H-VCCPLL)") (class "Default")
      (node (ref "C85") (pin "1") (pinfunction "1_1") (pintype "passive"))
      (node (ref "C86") (pin "1") (pinfunction "1_1") (pintype "passive"))
      (node (ref "L3") (pin "1") (pinfunction "1_1") (pintype "passive"))
      (node (ref "U1") (pin "G8") (pinfunction "VCCPLL_G8") (pintype "passive"))
    )
    (net (code "7") (name "VCCIO") (class "Default")
      (node (ref "C44") (pin "1") (pinfunction "1_1") (pintype "passive"))
      (node (ref "C45") (pin "1") (pinfunction "1_1") (pintype "passive"))
      (node (ref "C46") (pin "1") (pinfunction "1_1") (pintype "passive"))
      (node (ref "C47") (pin "1") (pinfunction "1_1") (pintype "passive"))
      (node (ref "C48") (pin "1") (pinfunction "1_1") (pintype "passive"))
      (node (ref "C49") (pin "1") (pinfunction "1_1") (pintype "passive"))
      (node (ref "C50") (pin "1") (pinfunction "1_1") (pintype "passive"))
      (node (ref "C51") (pin "1") (pinfunction "1_1") (pintype "passive"))
      (node (ref "C52") (pin "1") (pinfunction "1_1") (pintype "passive"))
      (node (ref "U1") (pin "N19") (pinfunction "VCCO_34_1_N19") (pintype "passive"))
      (node (ref "U1") (pin "R15") (pinfunction "VCCO_34_2_R15") (pintype "passive"))
      (node (ref "U1") (pin "T18") (pinfunction "VCCO_34_3_T18") (pintype "passive"))
      (node (ref "U1") (pin "V14") (pinfunction "VCCO_34_4_V14") (pintype "passive"))
      (node (ref "U1") (pin "W17") (pinfunction "VCCO_34_5_W17") (pintype "passive"))
      (node (ref "U1") (pin "Y20") (pinfunction "VCCO_34_6_Y20") (pintype "passive"))
    )
    (net (code "8") (name "VTTREF") (class "Default")
      (node (ref "C87") (pin "1") (pinfunction "1_1") (pintype "passive"))
      (node (ref "C88") (pin "1") (pinfunction "1_1") (pintype "passive"))
      (node (ref "U1") (pin "H6") (pinfunction "PS_DDR_VREF0_502_1_H6") (pintype "passive"))
      (node (ref "U1") (pin "P6") (pinfunction "PS_DDR_VREF0_502_2_P6") (pintype "passive"))
    )
  )
)
